# output_selector_v3.net
KiCad netlist of a schematic drawn in EAGLE
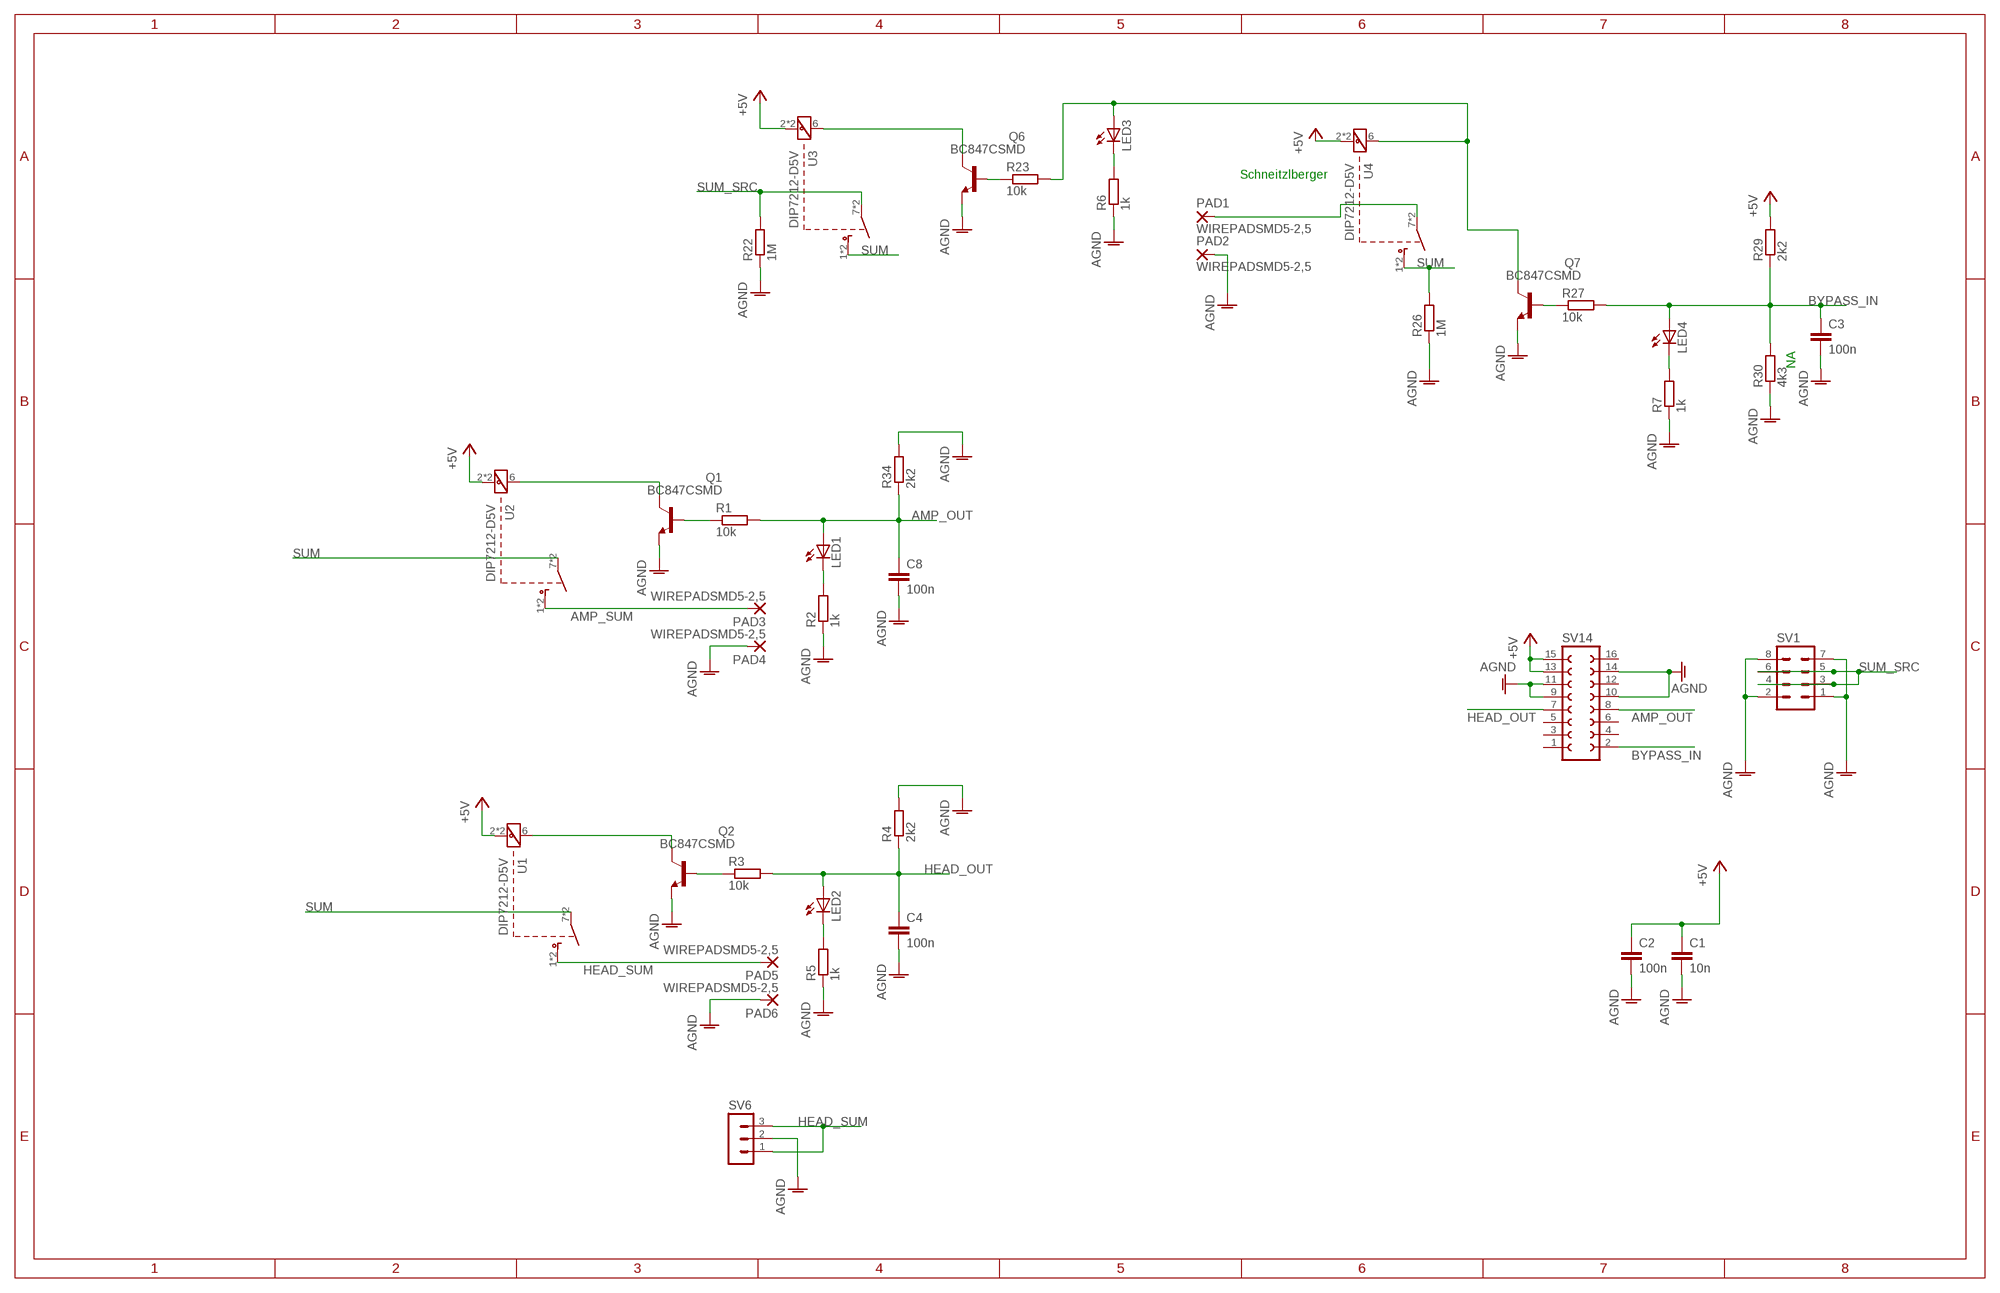
[diagram p0: schematic, sheet 1]

(export (version "E")
  (design (tool "Eeschema 10.0.6"))
  (components
    (comp (ref "C1")
      (value "10n")
      (footprint "eagle-import:C0603")
      (libsource (lib "eagle-import") (part "C-EUC0603"))
    )
    (comp (ref "C2")
      (value "100n")
      (footprint "eagle-import:C0603")
      (libsource (lib "eagle-import") (part "C-EUC0603"))
    )
    (comp (ref "C3")
      (value "100n")
      (footprint "eagle-import:C0603")
      (libsource (lib "eagle-import") (part "C-EUC0603"))
    )
    (comp (ref "C4")
      (value "100n")
      (footprint "eagle-import:C0603")
      (libsource (lib "eagle-import") (part "C-EUC0603"))
    )
    (comp (ref "C8")
      (value "100n")
      (footprint "eagle-import:C0603")
      (libsource (lib "eagle-import") (part "C-EUC0603"))
    )
    (comp (ref "LED1")
      (value "LEDCHIPLED_0603")
      (footprint "eagle-import:CHIPLED_0603")
      (libsource (lib "eagle-import") (part "LEDCHIPLED_0603"))
    )
    (comp (ref "LED2")
      (value "LEDCHIPLED_0603")
      (footprint "eagle-import:CHIPLED_0603")
      (libsource (lib "eagle-import") (part "LEDCHIPLED_0603"))
    )
    (comp (ref "LED3")
      (value "LEDCHIPLED_0603")
      (footprint "eagle-import:CHIPLED_0603")
      (libsource (lib "eagle-import") (part "LEDCHIPLED_0603"))
    )
    (comp (ref "LED4")
      (value "LEDCHIPLED_0603")
      (footprint "eagle-import:CHIPLED_0603")
      (libsource (lib "eagle-import") (part "LEDCHIPLED_0603"))
    )
    (comp (ref "PAD1")
      (value "WIREPADSMD5-2,5")
      (footprint "eagle-import:5-2,5")
      (libsource (lib "eagle-import") (part "WIREPADSMD5-2,5"))
    )
    (comp (ref "PAD2")
      (value "WIREPADSMD5-2,5")
      (footprint "eagle-import:5-2,5")
      (libsource (lib "eagle-import") (part "WIREPADSMD5-2,5"))
    )
    (comp (ref "PAD3")
      (value "WIREPADSMD5-2,5")
      (footprint "eagle-import:5-2,5")
      (libsource (lib "eagle-import") (part "WIREPADSMD5-2,5"))
    )
    (comp (ref "PAD4")
      (value "WIREPADSMD5-2,5")
      (footprint "eagle-import:5-2,5")
      (libsource (lib "eagle-import") (part "WIREPADSMD5-2,5"))
    )
    (comp (ref "PAD5")
      (value "WIREPADSMD5-2,5")
      (footprint "eagle-import:5-2,5")
      (libsource (lib "eagle-import") (part "WIREPADSMD5-2,5"))
    )
    (comp (ref "PAD6")
      (value "WIREPADSMD5-2,5")
      (footprint "eagle-import:5-2,5")
      (libsource (lib "eagle-import") (part "WIREPADSMD5-2,5"))
    )
    (comp (ref "Q1")
      (value "BC847CSMD")
      (footprint "eagle-import:SOT23")
      (libsource (lib "eagle-import") (part "BC847SMDC"))
    )
    (comp (ref "Q2")
      (value "BC847CSMD")
      (footprint "eagle-import:SOT23")
      (libsource (lib "eagle-import") (part "BC847SMDC"))
    )
    (comp (ref "Q6")
      (value "BC847CSMD")
      (footprint "eagle-import:SOT23")
      (libsource (lib "eagle-import") (part "BC847SMDC"))
    )
    (comp (ref "Q7")
      (value "BC847CSMD")
      (footprint "eagle-import:SOT23")
      (libsource (lib "eagle-import") (part "BC847SMDC"))
    )
    (comp (ref "R1")
      (value "10k")
      (footprint "eagle-import:R0603")
      (libsource (lib "eagle-import") (part "R-EU_R0603"))
    )
    (comp (ref "R2")
      (value "1k")
      (footprint "eagle-import:R0603")
      (libsource (lib "eagle-import") (part "R-EU_R0603"))
    )
    (comp (ref "R3")
      (value "10k")
      (footprint "eagle-import:R0603")
      (libsource (lib "eagle-import") (part "R-EU_R0603"))
    )
    (comp (ref "R4")
      (value "2k2")
      (footprint "eagle-import:R0603")
      (libsource (lib "eagle-import") (part "R-EU_R0603"))
    )
    (comp (ref "R5")
      (value "1k")
      (footprint "eagle-import:R0603")
      (libsource (lib "eagle-import") (part "R-EU_R0603"))
    )
    (comp (ref "R6")
      (value "1k")
      (footprint "eagle-import:R0603")
      (libsource (lib "eagle-import") (part "R-EU_R0603"))
    )
    (comp (ref "R7")
      (value "1k")
      (footprint "eagle-import:R0603")
      (libsource (lib "eagle-import") (part "R-EU_R0603"))
    )
    (comp (ref "R22")
      (value "1M")
      (footprint "eagle-import:R0603")
      (libsource (lib "eagle-import") (part "R-EU_R0603"))
    )
    (comp (ref "R23")
      (value "10k")
      (footprint "eagle-import:R0603")
      (libsource (lib "eagle-import") (part "R-EU_R0603"))
    )
    (comp (ref "R26")
      (value "1M")
      (footprint "eagle-import:R0603")
      (libsource (lib "eagle-import") (part "R-EU_R0603"))
    )
    (comp (ref "R27")
      (value "10k")
      (footprint "eagle-import:R0603")
      (libsource (lib "eagle-import") (part "R-EU_R0603"))
    )
    (comp (ref "R29")
      (value "2k2")
      (footprint "eagle-import:R0603")
      (libsource (lib "eagle-import") (part "R-EU_R0603"))
    )
    (comp (ref "R30")
      (value "4k3")
      (footprint "eagle-import:R0603")
      (libsource (lib "eagle-import") (part "R-EU_R0603"))
    )
    (comp (ref "R34")
      (value "2k2")
      (footprint "eagle-import:R0603")
      (libsource (lib "eagle-import") (part "R-EU_R0603"))
    )
    (comp (ref "SV1")
      (value "MA04-2W")
      (footprint "eagle-import:MA04-2W")
      (libsource (lib "eagle-import") (part "MA04-2W"))
    )
    (comp (ref "SV6")
      (value "MA03-1")
      (footprint "eagle-import:MA03-1")
      (libsource (lib "eagle-import") (part "MA03-1"))
    )
    (comp (ref "SV14")
      (value "FE08-2W")
      (footprint "eagle-import:FE08-2W")
      (libsource (lib "eagle-import") (part "FE08-2W"))
    )
    (comp (ref "U1")
      (value "DIP7212-D5V")
      (footprint "eagle-import:DP-07")
      (libsource (lib "eagle-import") (part "DIP7212-D5V"))
    )
    (comp (ref "U2")
      (value "DIP7212-D5V")
      (footprint "eagle-import:DP-07")
      (libsource (lib "eagle-import") (part "DIP7212-D5V"))
    )
    (comp (ref "U3")
      (value "DIP7212-D5V")
      (footprint "eagle-import:DP-07")
      (libsource (lib "eagle-import") (part "DIP7212-D5V"))
    )
    (comp (ref "U4")
      (value "DIP7212-D5V")
      (footprint "eagle-import:DP-07")
      (libsource (lib "eagle-import") (part "DIP7212-D5V"))
    )
  )
  (nets
    (net (code "1") (name "+5V") (class "Default")
      (node (ref "C1") (pin "1") (pinfunction "1_1") (pintype "passive"))
      (node (ref "C2") (pin "1") (pinfunction "1_1") (pintype "passive"))
      (node (ref "R29") (pin "2") (pinfunction "2_2") (pintype "passive"))
      (node (ref "SV14") (pin "13") (pinfunction "13_13") (pintype "passive"))
      (node (ref "SV14") (pin "15") (pinfunction "15_15") (pintype "passive"))
      (node (ref "U1") (pin "13") (pinfunction "1_13") (pintype "passive"))
      (node (ref "U1") (pin "2") (pinfunction "1_2") (pintype "passive"))
      (node (ref "U2") (pin "13") (pinfunction "1_13") (pintype "passive"))
      (node (ref "U2") (pin "2") (pinfunction "1_2") (pintype "passive"))
      (node (ref "U3") (pin "13") (pinfunction "1_13") (pintype "passive"))
      (node (ref "U3") (pin "2") (pinfunction "1_2") (pintype "passive"))
      (node (ref "U4") (pin "13") (pinfunction "1_13") (pintype "passive"))
      (node (ref "U4") (pin "2") (pinfunction "1_2") (pintype "passive"))
    )
    (net (code "2") (name "/AMP_OUT") (class "Default")
      (node (ref "C8") (pin "1") (pinfunction "1_1") (pintype "passive"))
      (node (ref "LED1") (pin "A") (pinfunction "A_A") (pintype "passive"))
      (node (ref "R1") (pin "2") (pinfunction "2_2") (pintype "passive"))
      (node (ref "R34") (pin "1") (pinfunction "1_1") (pintype "passive"))
      (node (ref "SV14") (pin "8") (pinfunction "8_8") (pintype "passive"))
    )
    (net (code "3") (name "/AMP_SUM") (class "Default")
      (node (ref "PAD3") (pin "1") (pinfunction "P_1") (pintype "passive"))
      (node (ref "U2") (pin "1") (pinfunction "6_1") (pintype "passive"))
      (node (ref "U2") (pin "14") (pinfunction "6_14") (pintype "passive"))
    )
    (net (code "4") (name "/BYPASS_IN") (class "Default")
      (node (ref "C3") (pin "1") (pinfunction "1_1") (pintype "passive"))
      (node (ref "LED4") (pin "A") (pinfunction "A_A") (pintype "passive"))
      (node (ref "R27") (pin "2") (pinfunction "2_2") (pintype "passive"))
      (node (ref "R29") (pin "1") (pinfunction "1_1") (pintype "passive"))
      (node (ref "R30") (pin "2") (pinfunction "2_2") (pintype "passive"))
      (node (ref "SV14") (pin "2") (pinfunction "2_2") (pintype "passive"))
    )
    (net (code "5") (name "/HEAD_OUT") (class "Default")
      (node (ref "C4") (pin "1") (pinfunction "1_1") (pintype "passive"))
      (node (ref "LED2") (pin "A") (pinfunction "A_A") (pintype "passive"))
      (node (ref "R3") (pin "2") (pinfunction "2_2") (pintype "passive"))
      (node (ref "R4") (pin "1") (pinfunction "1_1") (pintype "passive"))
      (node (ref "SV14") (pin "7") (pinfunction "7_7") (pintype "passive"))
    )
    (net (code "6") (name "/HEAD_SUM") (class "Default")
      (node (ref "PAD5") (pin "1") (pinfunction "P_1") (pintype "passive"))
      (node (ref "SV6") (pin "1") (pinfunction "1_1") (pintype "passive"))
      (node (ref "SV6") (pin "3") (pinfunction "3_3") (pintype "passive"))
      (node (ref "U1") (pin "1") (pinfunction "6_1") (pintype "passive"))
      (node (ref "U1") (pin "14") (pinfunction "6_14") (pintype "passive"))
    )
    (net (code "7") (name "/SUM") (class "Default")
      (node (ref "R26") (pin "2") (pinfunction "2_2") (pintype "passive"))
      (node (ref "U1") (pin "7") (pinfunction "5_7") (pintype "passive"))
      (node (ref "U1") (pin "8") (pinfunction "5_8") (pintype "passive"))
      (node (ref "U2") (pin "7") (pinfunction "5_7") (pintype "passive"))
      (node (ref "U2") (pin "8") (pinfunction "5_8") (pintype "passive"))
      (node (ref "U3") (pin "1") (pinfunction "6_1") (pintype "passive"))
      (node (ref "U3") (pin "14") (pinfunction "6_14") (pintype "passive"))
      (node (ref "U4") (pin "1") (pinfunction "6_1") (pintype "passive"))
      (node (ref "U4") (pin "14") (pinfunction "6_14") (pintype "passive"))
    )
    (net (code "8") (name "/SUM_SRC") (class "Default")
      (node (ref "R22") (pin "2") (pinfunction "2_2") (pintype "passive"))
      (node (ref "SV1") (pin "3") (pinfunction "3_3") (pintype "passive"))
      (node (ref "SV1") (pin "4") (pinfunction "4_4") (pintype "passive"))
      (node (ref "SV1") (pin "5") (pinfunction "5_5") (pintype "passive"))
      (node (ref "SV1") (pin "6") (pinfunction "6_6") (pintype "passive"))
      (node (ref "U3") (pin "7") (pinfunction "5_7") (pintype "passive"))
      (node (ref "U3") (pin "8") (pinfunction "5_8") (pintype "passive"))
    )
    (net (code "9") (name "AGND") (class "Default")
      (node (ref "C1") (pin "2") (pinfunction "2_2") (pintype "passive"))
      (node (ref "C2") (pin "2") (pinfunction "2_2") (pintype "passive"))
      (node (ref "C3") (pin "2") (pinfunction "2_2") (pintype "passive"))
      (node (ref "C4") (pin "2") (pinfunction "2_2") (pintype "passive"))
      (node (ref "C8") (pin "2") (pinfunction "2_2") (pintype "passive"))
      (node (ref "PAD2") (pin "1") (pinfunction "P_1") (pintype "passive"))
      (node (ref "PAD4") (pin "1") (pinfunction "P_1") (pintype "passive"))
      (node (ref "PAD6") (pin "1") (pinfunction "P_1") (pintype "passive"))
      (node (ref "Q1") (pin "2") (pinfunction "E_2") (pintype "passive"))
      (node (ref "Q2") (pin "2") (pinfunction "E_2") (pintype "passive"))
      (node (ref "Q6") (pin "2") (pinfunction "E_2") (pintype "passive"))
      (node (ref "Q7") (pin "2") (pinfunction "E_2") (pintype "passive"))
      (node (ref "R2") (pin "1") (pinfunction "1_1") (pintype "passive"))
      (node (ref "R22") (pin "1") (pinfunction "1_1") (pintype "passive"))
      (node (ref "R26") (pin "1") (pinfunction "1_1") (pintype "passive"))
      (node (ref "R30") (pin "1") (pinfunction "1_1") (pintype "passive"))
      (node (ref "R34") (pin "2") (pinfunction "2_2") (pintype "passive"))
      (node (ref "R4") (pin "2") (pinfunction "2_2") (pintype "passive"))
      (node (ref "R5") (pin "1") (pinfunction "1_1") (pintype "passive"))
      (node (ref "R6") (pin "1") (pinfunction "1_1") (pintype "passive"))
      (node (ref "R7") (pin "1") (pinfunction "1_1") (pintype "passive"))
      (node (ref "SV1") (pin "1") (pinfunction "1_1") (pintype "passive"))
      (node (ref "SV1") (pin "2") (pinfunction "2_2") (pintype "passive"))
      (node (ref "SV1") (pin "7") (pinfunction "7_7") (pintype "passive"))
      (node (ref "SV1") (pin "8") (pinfunction "8_8") (pintype "passive"))
      (node (ref "SV14") (pin "10") (pinfunction "10_10") (pintype "passive"))
      (node (ref "SV14") (pin "11") (pinfunction "11_11") (pintype "passive"))
      (node (ref "SV14") (pin "14") (pinfunction "14_14") (pintype "passive"))
      (node (ref "SV14") (pin "9") (pinfunction "9_9") (pintype "passive"))
      (node (ref "SV6") (pin "2") (pinfunction "2_2") (pintype "passive"))
    )
    (net (code "10") (name "Net-(LED1-PadC)") (class "Default")
      (node (ref "LED1") (pin "C") (pinfunction "C_C") (pintype "passive"))
      (node (ref "R2") (pin "2") (pinfunction "2_2") (pintype "passive"))
    )
    (net (code "11") (name "Net-(LED2-PadC)") (class "Default")
      (node (ref "LED2") (pin "C") (pinfunction "C_C") (pintype "passive"))
      (node (ref "R5") (pin "2") (pinfunction "2_2") (pintype "passive"))
    )
    (net (code "12") (name "Net-(LED3-PadC)") (class "Default")
      (node (ref "LED3") (pin "C") (pinfunction "C_C") (pintype "passive"))
      (node (ref "R6") (pin "2") (pinfunction "2_2") (pintype "passive"))
    )
    (net (code "13") (name "Net-(LED4-PadC)") (class "Default")
      (node (ref "LED4") (pin "C") (pinfunction "C_C") (pintype "passive"))
      (node (ref "R7") (pin "2") (pinfunction "2_2") (pintype "passive"))
    )
    (net (code "14") (name "Net-(PAD1-P)") (class "Default")
      (node (ref "PAD1") (pin "1") (pinfunction "P_1") (pintype "passive"))
      (node (ref "U4") (pin "7") (pinfunction "5_7") (pintype "passive"))
      (node (ref "U4") (pin "8") (pinfunction "5_8") (pintype "passive"))
    )
    (net (code "15") (name "Net-(Q1-B)") (class "Default")
      (node (ref "Q1") (pin "1") (pinfunction "B_1") (pintype "passive"))
      (node (ref "R1") (pin "1") (pinfunction "1_1") (pintype "passive"))
    )
    (net (code "16") (name "Net-(Q1-C)") (class "Default")
      (node (ref "Q1") (pin "3") (pinfunction "C_3") (pintype "passive"))
      (node (ref "U2") (pin "6") (pinfunction "2_6") (pintype "passive"))
    )
    (net (code "17") (name "Net-(Q2-B)") (class "Default")
      (node (ref "Q2") (pin "1") (pinfunction "B_1") (pintype "passive"))
      (node (ref "R3") (pin "1") (pinfunction "1_1") (pintype "passive"))
    )
    (net (code "18") (name "Net-(Q2-C)") (class "Default")
      (node (ref "Q2") (pin "3") (pinfunction "C_3") (pintype "passive"))
      (node (ref "U1") (pin "6") (pinfunction "2_6") (pintype "passive"))
    )
    (net (code "19") (name "Net-(Q6-B)") (class "Default")
      (node (ref "Q6") (pin "1") (pinfunction "B_1") (pintype "passive"))
      (node (ref "R23") (pin "1") (pinfunction "1_1") (pintype "passive"))
    )
    (net (code "20") (name "Net-(Q6-C)") (class "Default")
      (node (ref "Q6") (pin "3") (pinfunction "C_3") (pintype "passive"))
      (node (ref "U3") (pin "6") (pinfunction "2_6") (pintype "passive"))
    )
    (net (code "21") (name "Net-(Q7-B)") (class "Default")
      (node (ref "Q7") (pin "1") (pinfunction "B_1") (pintype "passive"))
      (node (ref "R27") (pin "1") (pinfunction "1_1") (pintype "passive"))
    )
    (net (code "22") (name "Net-(Q7-C)") (class "Default")
      (node (ref "LED3") (pin "A") (pinfunction "A_A") (pintype "passive"))
      (node (ref "Q7") (pin "3") (pinfunction "C_3") (pintype "passive"))
      (node (ref "R23") (pin "2") (pinfunction "2_2") (pintype "passive"))
      (node (ref "U4") (pin "6") (pinfunction "2_6") (pintype "passive"))
    )
    (net (code "23") (name "unconnected-(SV14-Pad1)") (class "Default")
      (node (ref "SV14") (pin "1") (pinfunction "1_1") (pintype "passive"))
    )
    (net (code "24") (name "unconnected-(SV14-Pad3)") (class "Default")
      (node (ref "SV14") (pin "3") (pinfunction "3_3") (pintype "passive"))
    )
    (net (code "25") (name "unconnected-(SV14-Pad4)") (class "Default")
      (node (ref "SV14") (pin "4") (pinfunction "4_4") (pintype "passive"))
    )
    (net (code "26") (name "unconnected-(SV14-Pad5)") (class "Default")
      (node (ref "SV14") (pin "5") (pinfunction "5_5") (pintype "passive"))
    )
    (net (code "27") (name "unconnected-(SV14-Pad6)") (class "Default")
      (node (ref "SV14") (pin "6") (pinfunction "6_6") (pintype "passive"))
    )
    (net (code "28") (name "unconnected-(SV14-Pad12)") (class "Default")
      (node (ref "SV14") (pin "12") (pinfunction "12_12") (pintype "passive"))
    )
    (net (code "29") (name "unconnected-(SV14-Pad16)") (class "Default")
      (node (ref "SV14") (pin "16") (pinfunction "16_16") (pintype "passive"))
    )
  )
)
